# 11Dof_MPU6000.net
KiCad netlist of a schematic drawn in EAGLE
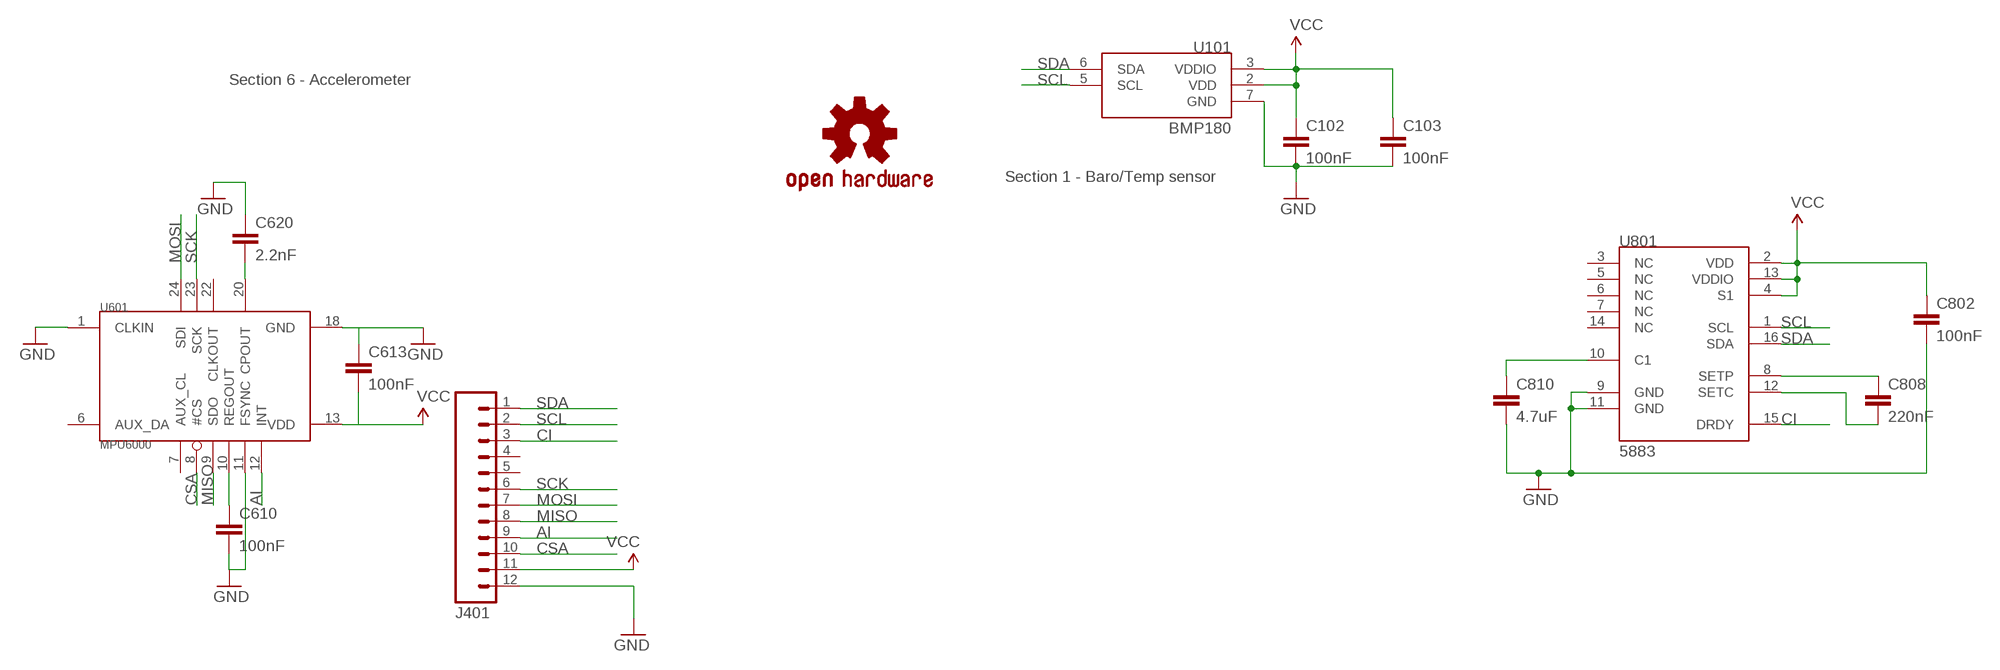
[diagram p0: schematic, sheet 1]

(export (version "E")
  (design (tool "Eeschema 10.0.6"))
  (components
    (comp (ref "C102")
      (value "100nF")
      (footprint "eagle-import:0603-CAP")
      (libsource (lib "eagle-import") (part "CAP0603-CAP"))
    )
    (comp (ref "C103")
      (value "100nF")
      (footprint "eagle-import:0603-CAP")
      (libsource (lib "eagle-import") (part "CAP0603-CAP"))
    )
    (comp (ref "C610")
      (value "100nF")
      (footprint "eagle-import:0603-CAP")
      (libsource (lib "eagle-import") (part "CAP0603-CAP"))
    )
    (comp (ref "C613")
      (value "100nF")
      (footprint "eagle-import:0603-CAP")
      (libsource (lib "eagle-import") (part "CAP0603-CAP"))
    )
    (comp (ref "C620")
      (value "2.2nF")
      (footprint "eagle-import:0603-CAP")
      (libsource (lib "eagle-import") (part "CAP0603-CAP"))
    )
    (comp (ref "C802")
      (value "100nF")
      (footprint "eagle-import:0603-CAP")
      (libsource (lib "eagle-import") (part "CAP0603-CAP"))
    )
    (comp (ref "C808")
      (value "220nF")
      (footprint "eagle-import:0603-CAP")
      (libsource (lib "eagle-import") (part "CAP0603-CAP"))
    )
    (comp (ref "C810")
      (value "4.7uF")
      (footprint "eagle-import:0603-CAP")
      (libsource (lib "eagle-import") (part "CAP0603-CAP"))
    )
    (comp (ref "J401")
      (value "M12PTH")
      (footprint "eagle-import:1X12")
      (libsource (lib "eagle-import") (part "M12PTH"))
    )
    (comp (ref "U$2")
      (value "OSHW-LOGOS")
      (footprint "eagle-import:OSHW-LOGO-S")
      (libsource (lib "eagle-import") (part "OSHW-LOGOS"))
    )
    (comp (ref "U101")
      (value "BMP180")
      (footprint "eagle-import:BMP180")
      (libsource (lib "eagle-import") (part "BMP180"))
    )
    (comp (ref "U601")
      (value "MPU6000")
      (footprint "eagle-import:MPU60X0")
      (libsource (lib "eagle-import") (part "MPU6000"))
    )
    (comp (ref "U801")
      (value "5883")
      (footprint "eagle-import:16LPCC")
      (libsource (lib "eagle-import") (part "HMC5883LSMD"))
    )
  )
  (nets
    (net (code "1") (name "/AI") (class "Default")
      (node (ref "J401") (pin "9") (pinfunction "9_9") (pintype "passive"))
      (node (ref "U601") (pin "12") (pinfunction "INT_12") (pintype "output"))
    )
    (net (code "2") (name "/CI") (class "Default")
      (node (ref "J401") (pin "3") (pinfunction "3_3") (pintype "passive"))
      (node (ref "U801") (pin "15") (pinfunction "DRDY_15") (pintype "bidirectional"))
    )
    (net (code "3") (name "/CSA") (class "Default")
      (node (ref "J401") (pin "10") (pinfunction "10_10") (pintype "passive"))
      (node (ref "U601") (pin "8") (pinfunction "#CS_8") (pintype "bidirectional"))
    )
    (net (code "4") (name "/MISO") (class "Default")
      (node (ref "J401") (pin "8") (pinfunction "8_8") (pintype "passive"))
      (node (ref "U601") (pin "9") (pinfunction "SDO_9") (pintype "output"))
    )
    (net (code "5") (name "/MOSI") (class "Default")
      (node (ref "J401") (pin "7") (pinfunction "7_7") (pintype "passive"))
      (node (ref "U601") (pin "24") (pinfunction "SDI_24") (pintype "bidirectional"))
    )
    (net (code "6") (name "/SCK") (class "Default")
      (node (ref "J401") (pin "6") (pinfunction "6_6") (pintype "passive"))
      (node (ref "U601") (pin "23") (pinfunction "SCK_23") (pintype "bidirectional"))
    )
    (net (code "7") (name "/SCL") (class "Default")
      (node (ref "J401") (pin "2") (pinfunction "2_2") (pintype "passive"))
      (node (ref "U101") (pin "5") (pinfunction "SCL_5") (pintype "input"))
      (node (ref "U801") (pin "1") (pinfunction "SCL_1") (pintype "bidirectional"))
    )
    (net (code "8") (name "/SDA") (class "Default")
      (node (ref "J401") (pin "1") (pinfunction "1_1") (pintype "passive"))
      (node (ref "U101") (pin "6") (pinfunction "SDA_6") (pintype "bidirectional"))
      (node (ref "U801") (pin "16") (pinfunction "SDA_16") (pintype "bidirectional"))
    )
    (net (code "9") (name "GND") (class "Default")
      (node (ref "C102") (pin "2") (pinfunction "2_2") (pintype "passive"))
      (node (ref "C103") (pin "2") (pinfunction "2_2") (pintype "passive"))
      (node (ref "C610") (pin "2") (pinfunction "2_2") (pintype "passive"))
      (node (ref "C613") (pin "1") (pinfunction "1_1") (pintype "passive"))
      (node (ref "C620") (pin "1") (pinfunction "1_1") (pintype "passive"))
      (node (ref "C802") (pin "2") (pinfunction "2_2") (pintype "passive"))
      (node (ref "C810") (pin "2") (pinfunction "2_2") (pintype "passive"))
      (node (ref "J401") (pin "12") (pinfunction "12_12") (pintype "passive"))
      (node (ref "U101") (pin "7") (pinfunction "GND_7") (pintype "power_in"))
      (node (ref "U601") (pin "1") (pinfunction "CLKIN_1") (pintype "input"))
      (node (ref "U601") (pin "11") (pinfunction "FSYNC_11") (pintype "bidirectional"))
      (node (ref "U601") (pin "18") (pinfunction "GND_18") (pintype "power_in"))
      (node (ref "U801") (pin "11") (pinfunction "GND_11") (pintype "bidirectional"))
      (node (ref "U801") (pin "9") (pinfunction "GND_9") (pintype "bidirectional"))
    )
    (net (code "10") (name "Net-(U601-CPOUT)") (class "Default")
      (node (ref "C620") (pin "2") (pinfunction "2_2") (pintype "passive"))
      (node (ref "U601") (pin "20") (pinfunction "CPOUT_20") (pintype "output"))
    )
    (net (code "11") (name "Net-(U601-REGOUT)") (class "Default")
      (node (ref "C610") (pin "1") (pinfunction "1_1") (pintype "passive"))
      (node (ref "U601") (pin "10") (pinfunction "REGOUT_10") (pintype "bidirectional"))
    )
    (net (code "12") (name "Net-(U801-C1)") (class "Default")
      (node (ref "C810") (pin "1") (pinfunction "1_1") (pintype "passive"))
      (node (ref "U801") (pin "10") (pinfunction "C1_10") (pintype "bidirectional"))
    )
    (net (code "13") (name "Net-(U801-SETC)") (class "Default")
      (node (ref "C808") (pin "2") (pinfunction "2_2") (pintype "passive"))
      (node (ref "U801") (pin "12") (pinfunction "SETC_12") (pintype "bidirectional"))
    )
    (net (code "14") (name "Net-(U801-SETP)") (class "Default")
      (node (ref "C808") (pin "1") (pinfunction "1_1") (pintype "passive"))
      (node (ref "U801") (pin "8") (pinfunction "SETP_8") (pintype "bidirectional"))
    )
    (net (code "15") (name "VCC") (class "Default")
      (node (ref "C102") (pin "1") (pinfunction "1_1") (pintype "passive"))
      (node (ref "C103") (pin "1") (pinfunction "1_1") (pintype "passive"))
      (node (ref "C613") (pin "2") (pinfunction "2_2") (pintype "passive"))
      (node (ref "C802") (pin "1") (pinfunction "1_1") (pintype "passive"))
      (node (ref "J401") (pin "11") (pinfunction "11_11") (pintype "passive"))
      (node (ref "U101") (pin "2") (pinfunction "VDD_2") (pintype "power_in"))
      (node (ref "U101") (pin "3") (pinfunction "VDDIO_3") (pintype "power_in"))
      (node (ref "U601") (pin "13") (pinfunction "VDD_13") (pintype "power_in"))
      (node (ref "U801") (pin "13") (pinfunction "VDDIO_13") (pintype "bidirectional"))
      (node (ref "U801") (pin "2") (pinfunction "VDD_2") (pintype "bidirectional"))
      (node (ref "U801") (pin "4") (pinfunction "S1_4") (pintype "bidirectional"))
    )
    (net (code "16") (name "unconnected-(J401-Pad4)") (class "Default")
      (node (ref "J401") (pin "4") (pinfunction "4_4") (pintype "passive"))
    )
    (net (code "17") (name "unconnected-(J401-Pad5)") (class "Default")
      (node (ref "J401") (pin "5") (pinfunction "5_5") (pintype "passive"))
    )
    (net (code "18") (name "unconnected-(U601-AUX_CL-Pad7)") (class "Default")
      (node (ref "U601") (pin "7") (pinfunction "AUX_CL_7") (pintype "bidirectional"))
    )
    (net (code "19") (name "unconnected-(U601-AUX_DA-Pad6)") (class "Default")
      (node (ref "U601") (pin "6") (pinfunction "AUX_DA_6") (pintype "bidirectional"))
    )
    (net (code "20") (name "unconnected-(U601-CLKOUT-Pad22)") (class "Default")
      (node (ref "U601") (pin "22") (pinfunction "CLKOUT_22") (pintype "bidirectional"))
    )
    (net (code "21") (name "unconnected-(U801-NC-Pad3)") (class "Default")
      (node (ref "U801") (pin "3") (pinfunction "NC_3") (pintype "bidirectional"))
    )
    (net (code "22") (name "unconnected-(U801-NC-Pad5)") (class "Default")
      (node (ref "U801") (pin "5") (pinfunction "NC_5") (pintype "bidirectional"))
    )
    (net (code "23") (name "unconnected-(U801-NC-Pad6)") (class "Default")
      (node (ref "U801") (pin "6") (pinfunction "NC_6") (pintype "bidirectional"))
    )
    (net (code "24") (name "unconnected-(U801-NC-Pad7)") (class "Default")
      (node (ref "U801") (pin "7") (pinfunction "NC_7") (pintype "bidirectional"))
    )
    (net (code "25") (name "unconnected-(U801-NC-Pad14)") (class "Default")
      (node (ref "U801") (pin "14") (pinfunction "NC_14") (pintype "bidirectional"))
    )
  )
)
